# Isolation.net
KiCad netlist of a schematic drawn in Altium Designer
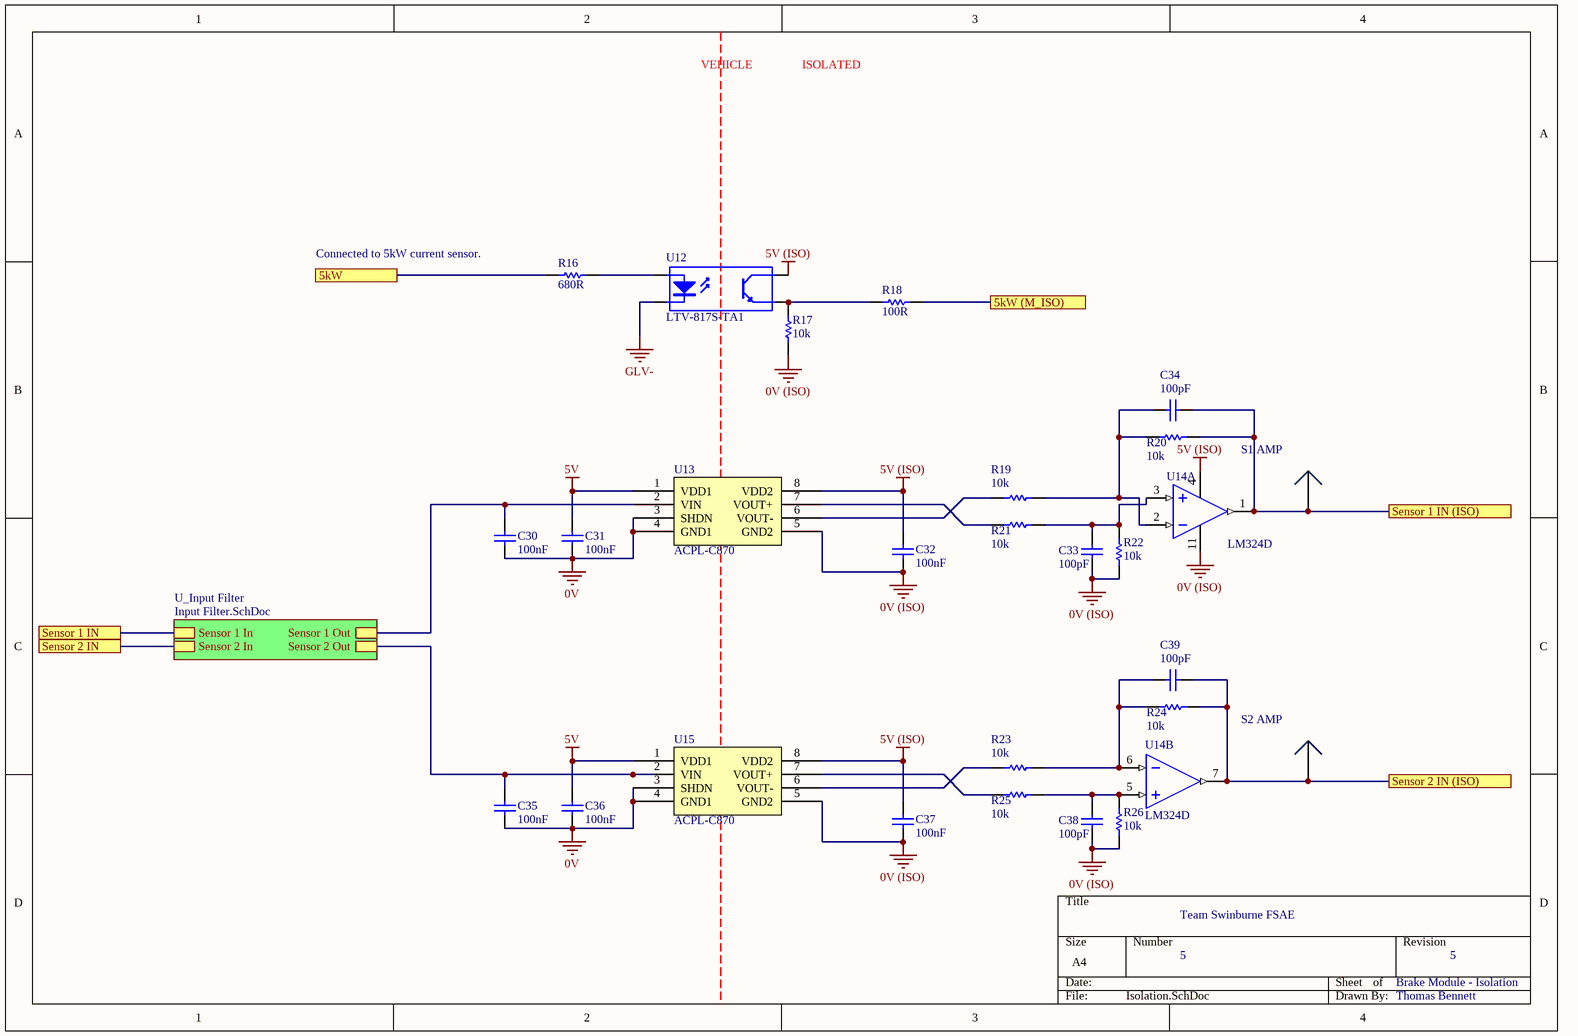
[diagram p0: Isolation.SchDoc]

(export (version "E")
  (design (tool "Eeschema 10.0.6"))
  (components
    (comp (ref "C30")
      (value "100nF")
      (footprint "0805")
      (fields
        (field (name "PART NUMBER") "GCM21BR71H104KA37L")
        (field (name "TOLERANCE") "±10%")
        (field (name "MANUFACTURER") "muRata")
      )
      (libsource (lib "ts_20-standard-library") (part "Capacitor"))
    )
    (comp (ref "C31")
      (value "100nF")
      (footprint "0805")
      (fields
        (field (name "PART NUMBER") "GCM21BR71H104KA37L")
        (field (name "TOLERANCE") "±10%")
        (field (name "MANUFACTURER") "muRata")
      )
      (libsource (lib "ts_20-standard-library") (part "Capacitor"))
    )
    (comp (ref "C32")
      (value "100nF")
      (footprint "0805")
      (fields
        (field (name "PART NUMBER") "GCM21BR71H104KA37L")
        (field (name "TOLERANCE") "±10%")
        (field (name "MANUFACTURER") "muRata")
      )
      (libsource (lib "ts_20-standard-library") (part "Capacitor"))
    )
    (comp (ref "C33")
      (value "100pF")
      (footprint "0805")
      (fields
        (field (name "PART NUMBER") "GCM2165C1H101JA16D")
        (field (name "TOLERANCE") "±5%")
        (field (name "MANUFACTURER") "muRata")
      )
      (libsource (lib "ts_20-standard-library") (part "Capacitor"))
    )
    (comp (ref "C34")
      (value "100pF")
      (footprint "0805")
      (fields
        (field (name "PART NUMBER") "GCM2165C1H101JA16D")
        (field (name "TOLERANCE") "±5%")
        (field (name "MANUFACTURER") "muRata")
      )
      (libsource (lib "ts_20-standard-library") (part "Capacitor"))
    )
    (comp (ref "C35")
      (value "100nF")
      (footprint "0805")
      (fields
        (field (name "PART NUMBER") "GCM21BR71H104KA37L")
        (field (name "TOLERANCE") "±10%")
        (field (name "MANUFACTURER") "muRata")
      )
      (libsource (lib "ts_20-standard-library") (part "Capacitor"))
    )
    (comp (ref "C36")
      (value "100nF")
      (footprint "0805")
      (fields
        (field (name "PART NUMBER") "GCM21BR71H104KA37L")
        (field (name "TOLERANCE") "±10%")
        (field (name "MANUFACTURER") "muRata")
      )
      (libsource (lib "ts_20-standard-library") (part "Capacitor"))
    )
    (comp (ref "C37")
      (value "100nF")
      (footprint "0805")
      (fields
        (field (name "PART NUMBER") "GCM21BR71H104KA37L")
        (field (name "TOLERANCE") "±10%")
        (field (name "MANUFACTURER") "muRata")
      )
      (libsource (lib "ts_20-standard-library") (part "Capacitor"))
    )
    (comp (ref "C38")
      (value "100pF")
      (footprint "0805")
      (fields
        (field (name "PART NUMBER") "GCM2165C1H101JA16D")
        (field (name "TOLERANCE") "±5%")
        (field (name "MANUFACTURER") "muRata")
      )
      (libsource (lib "ts_20-standard-library") (part "Capacitor"))
    )
    (comp (ref "C39")
      (value "100pF")
      (footprint "0805")
      (fields
        (field (name "PART NUMBER") "GCM2165C1H101JA16D")
        (field (name "TOLERANCE") "±5%")
        (field (name "MANUFACTURER") "muRata")
      )
      (libsource (lib "ts_20-standard-library") (part "Capacitor"))
    )
    (comp (ref "R16")
      (value "680R")
      (footprint "0805")
      (fields
        (field (name "PART NUMBER") "RC0805FR07680RL")
        (field (name "MANUFACTURER") "YAGEO")
        (field (name "TOLERANCE") "0.01")
      )
      (libsource (lib "ts_20-standard-library") (part "Resistor"))
    )
    (comp (ref "R17")
      (value "10k")
      (footprint "0805")
      (fields
        (field (name "PART NUMBER") "RC0805FR0710KL")
        (field (name "MANUFACTURER") "YAGEO")
        (field (name "TOLERANCE") "0.01")
      )
      (libsource (lib "ts_20-standard-library") (part "Resistor"))
    )
    (comp (ref "R18")
      (value "100R")
      (footprint "0805")
      (fields
        (field (name "PART NUMBER") "RC0805FR07100RL")
        (field (name "MANUFACTURER") "YAGEO")
        (field (name "TOLERANCE") "0.01")
      )
      (libsource (lib "ts_20-standard-library") (part "Resistor"))
    )
    (comp (ref "R19")
      (value "10k")
      (footprint "0805")
      (fields
        (field (name "PART NUMBER") "RC0805FR0710KL")
        (field (name "MANUFACTURER") "YAGEO")
        (field (name "TOLERANCE") "0.01")
      )
      (libsource (lib "ts_20-standard-library") (part "Resistor"))
    )
    (comp (ref "R20")
      (value "10k")
      (footprint "0805")
      (fields
        (field (name "PART NUMBER") "RC0805FR0710KL")
        (field (name "MANUFACTURER") "YAGEO")
        (field (name "TOLERANCE") "0.01")
      )
      (libsource (lib "ts_20-standard-library") (part "Resistor"))
    )
    (comp (ref "R21")
      (value "10k")
      (footprint "0805")
      (fields
        (field (name "PART NUMBER") "RC0805FR0710KL")
        (field (name "MANUFACTURER") "YAGEO")
        (field (name "TOLERANCE") "0.01")
      )
      (libsource (lib "ts_20-standard-library") (part "Resistor"))
    )
    (comp (ref "R22")
      (value "10k")
      (footprint "0805")
      (fields
        (field (name "PART NUMBER") "RC0805FR0710KL")
        (field (name "MANUFACTURER") "YAGEO")
        (field (name "TOLERANCE") "0.01")
      )
      (libsource (lib "ts_20-standard-library") (part "Resistor"))
    )
    (comp (ref "R23")
      (value "10k")
      (footprint "0805")
      (fields
        (field (name "PART NUMBER") "RC0805FR0710KL")
        (field (name "MANUFACTURER") "YAGEO")
        (field (name "TOLERANCE") "0.01")
      )
      (libsource (lib "ts_20-standard-library") (part "Resistor"))
    )
    (comp (ref "R24")
      (value "10k")
      (footprint "0805")
      (fields
        (field (name "PART NUMBER") "RC0805FR0710KL")
        (field (name "MANUFACTURER") "YAGEO")
        (field (name "TOLERANCE") "0.01")
      )
      (libsource (lib "ts_20-standard-library") (part "Resistor"))
    )
    (comp (ref "R25")
      (value "10k")
      (footprint "0805")
      (fields
        (field (name "PART NUMBER") "RC0805FR0710KL")
        (field (name "MANUFACTURER") "YAGEO")
        (field (name "TOLERANCE") "0.01")
      )
      (libsource (lib "ts_20-standard-library") (part "Resistor"))
    )
    (comp (ref "R26")
      (value "10k")
      (footprint "0805")
      (fields
        (field (name "PART NUMBER") "RC0805FR0710KL")
        (field (name "MANUFACTURER") "YAGEO")
        (field (name "TOLERANCE") "0.01")
      )
      (libsource (lib "ts_20-standard-library") (part "Resistor"))
    )
    (comp (ref "S1 AMP")
      (value "0mm")
      (footprint "SMD Test Point")
      (fields (field (name "PART NUMBER") "SMD Test Point") (field (name "CONTACT") "NA"))
      (libsource (lib "ts_20-standard-connectors") (part "Test Point"))
    )
    (comp (ref "S2 AMP")
      (value "0mm")
      (footprint "SMD Test Point")
      (fields (field (name "PART NUMBER") "SMD Test Point") (field (name "CONTACT") "NA"))
      (libsource (lib "ts_20-standard-connectors") (part "Test Point"))
    )
    (comp (ref "U12")
      (value "LTV-817S-TA1")
      (footprint "ON 4-SMD")
      (description "35V 50ma Optocoupler (VF=1.2V)")
      (fields
        (field (name "MANUFACTURER") "Lite-On Inc")
        (field (name "DIGIKEY PART NUMBER") "160-1893-2-ND")
      )
      (libsource (lib "ts_20-standard-library") (part "LTV-817S-TA1"))
    )
    (comp (ref "U13")
      (value "ACPL-C870")
      (footprint "BROAD 8-SOIC")
      (description "Isolation Amplifier 1 Circuit Differential 8-SO")
      (fields
        (field (name "MANUFACTURER") "Broadcom Limited")
        (field (name "DIGIKEY PART NUMBER") "516-2578-5-ND")
      )
      (libsource (lib "ts_20-standard-library") (part "ACPL-C870"))
    )
    (comp (ref "U14")
      (value "LM324D")
      (footprint "TI 14-SOIC")
      (description "IC OPAMP GP 4 CIRCUIT 14SOIC")
      (fields
        (field (name "MANUFACTURER") "Texas Instruments")
        (field (name "DIGIKEY PART NUMBER") "296-1390-5-ND")
      )
      (libsource (lib "ts_20-standard-library") (part "LM324D"))
    )
    (comp (ref "U15")
      (value "ACPL-C870")
      (footprint "BROAD 8-SOIC")
      (description "Isolation Amplifier 1 Circuit Differential 8-SO")
      (fields
        (field (name "MANUFACTURER") "Broadcom Limited")
        (field (name "DIGIKEY PART NUMBER") "516-2578-5-ND")
      )
      (libsource (lib "ts_20-standard-library") (part "ACPL-C870"))
    )
  )
  (nets
    (net (code "1") (name "/5kW") (class "Default")
      (node (ref "R16") (pin "2") (pinfunction "2_2") (pintype "passive"))
    )
    (net (code "2") (name "/5kW (M_ISO)") (class "Default")
      (node (ref "R18") (pin "1") (pinfunction "1_1") (pintype "passive"))
    )
    (net (code "4") (name "/Sensor 1 IN (ISO)") (class "Default")
      (node (ref "C34") (pin "1") (pinfunction "1_1") (pintype "passive"))
      (node (ref "R20") (pin "2") (pinfunction "2_2") (pintype "passive"))
      (node (ref "S1 AMP") (pin "1") (pinfunction "1_1") (pintype "passive"))
      (node (ref "U14") (pin "1") (pinfunction "1OUT_1") (pintype "output"))
    )
    (net (code "5") (name "/Sensor 1 Out") (class "Default")
      (node (ref "C30") (pin "2") (pinfunction "2_2") (pintype "passive"))
      (node (ref "U13") (pin "2") (pinfunction "VIN_2") (pintype "passive"))
    )
    (net (code "7") (name "/Sensor 2 IN (ISO)") (class "Default")
      (node (ref "C39") (pin "1") (pinfunction "1_1") (pintype "passive"))
      (node (ref "R24") (pin "2") (pinfunction "2_2") (pintype "passive"))
      (node (ref "S2 AMP") (pin "1") (pinfunction "1_1") (pintype "passive"))
      (node (ref "U14") (pin "7") (pinfunction "2OUT_7") (pintype "output"))
    )
    (net (code "8") (name "/Sensor 2 Out") (class "Default")
      (node (ref "C35") (pin "2") (pinfunction "2_2") (pintype "passive"))
      (node (ref "U15") (pin "2") (pinfunction "VIN_2") (pintype "passive"))
    )
    (net (code "9") (name "0V") (class "Default")
      (node (ref "C30") (pin "1") (pinfunction "1_1") (pintype "passive"))
      (node (ref "C31") (pin "1") (pinfunction "1_1") (pintype "passive"))
      (node (ref "C35") (pin "1") (pinfunction "1_1") (pintype "passive"))
      (node (ref "C36") (pin "1") (pinfunction "1_1") (pintype "passive"))
      (node (ref "U13") (pin "3") (pinfunction "SHDN_3") (pintype "passive"))
      (node (ref "U13") (pin "4") (pinfunction "GND1_4") (pintype "passive"))
      (node (ref "U15") (pin "3") (pinfunction "SHDN_3") (pintype "passive"))
      (node (ref "U15") (pin "4") (pinfunction "GND1_4") (pintype "passive"))
    )
    (net (code "10") (name "0V (ISO)") (class "Default")
      (node (ref "C32") (pin "1") (pinfunction "1_1") (pintype "passive"))
      (node (ref "C33") (pin "1") (pinfunction "1_1") (pintype "passive"))
      (node (ref "C37") (pin "1") (pinfunction "1_1") (pintype "passive"))
      (node (ref "C38") (pin "1") (pinfunction "1_1") (pintype "passive"))
      (node (ref "R17") (pin "1") (pinfunction "1_1") (pintype "passive"))
      (node (ref "R22") (pin "1") (pinfunction "1_1") (pintype "passive"))
      (node (ref "R26") (pin "1") (pinfunction "1_1") (pintype "passive"))
      (node (ref "U13") (pin "5") (pinfunction "GND2_5") (pintype "passive"))
      (node (ref "U14") (pin "11") (pinfunction "GND_11") (pintype "power_in"))
      (node (ref "U15") (pin "5") (pinfunction "GND2_5") (pintype "passive"))
    )
    (net (code "11") (name "5V") (class "Default")
      (node (ref "C31") (pin "2") (pinfunction "2_2") (pintype "passive"))
      (node (ref "C36") (pin "2") (pinfunction "2_2") (pintype "passive"))
      (node (ref "U13") (pin "1") (pinfunction "VDD1_1") (pintype "passive"))
      (node (ref "U15") (pin "1") (pinfunction "VDD1_1") (pintype "passive"))
    )
    (net (code "12") (name "5V (ISO)") (class "Default")
      (node (ref "C32") (pin "2") (pinfunction "2_2") (pintype "passive"))
      (node (ref "C37") (pin "2") (pinfunction "2_2") (pintype "passive"))
      (node (ref "U12") (pin "4") (pinfunction "C_4") (pintype "passive"))
      (node (ref "U13") (pin "8") (pinfunction "VDD2_8") (pintype "passive"))
      (node (ref "U14") (pin "4") (pinfunction "VCC_4") (pintype "power_in"))
      (node (ref "U15") (pin "8") (pinfunction "VDD2_8") (pintype "passive"))
    )
    (net (code "13") (name "GLV-") (class "Default")
      (node (ref "U12") (pin "2") (pinfunction "K_2") (pintype "passive"))
    )
    (net (code "14") (name "Net-(C33-Pad2)") (class "Default")
      (node (ref "C33") (pin "2") (pinfunction "2_2") (pintype "passive"))
      (node (ref "R21") (pin "2") (pinfunction "2_2") (pintype "passive"))
      (node (ref "R22") (pin "2") (pinfunction "2_2") (pintype "passive"))
      (node (ref "U14") (pin "3") (pinfunction "1IN+_3") (pintype "input"))
    )
    (net (code "15") (name "Net-(C34-Pad2)") (class "Default")
      (node (ref "C34") (pin "2") (pinfunction "2_2") (pintype "passive"))
      (node (ref "R19") (pin "2") (pinfunction "2_2") (pintype "passive"))
      (node (ref "R20") (pin "1") (pinfunction "1_1") (pintype "passive"))
      (node (ref "U14") (pin "2") (pinfunction "1IN+_2") (pintype "input"))
    )
    (net (code "16") (name "Net-(U12-A)") (class "Default")
      (node (ref "R16") (pin "1") (pinfunction "1_1") (pintype "passive"))
      (node (ref "U12") (pin "1") (pinfunction "A_1") (pintype "passive"))
    )
    (net (code "17") (name "Net-(U12-E)") (class "Default")
      (node (ref "R17") (pin "2") (pinfunction "2_2") (pintype "passive"))
      (node (ref "R18") (pin "2") (pinfunction "2_2") (pintype "passive"))
      (node (ref "U12") (pin "3") (pinfunction "E_3") (pintype "passive"))
    )
    (net (code "18") (name "Net-(U13-VOUT+)") (class "Default")
      (node (ref "R21") (pin "1") (pinfunction "1_1") (pintype "passive"))
      (node (ref "U13") (pin "7") (pinfunction "VOUT+_7") (pintype "passive"))
    )
    (net (code "19") (name "Net-(U13-VOUT-)") (class "Default")
      (node (ref "R19") (pin "1") (pinfunction "1_1") (pintype "passive"))
      (node (ref "U13") (pin "6") (pinfunction "VOUT-_6") (pintype "passive"))
    )
    (net (code "20") (name "Net-(U14B-2IN+)") (class "Default")
      (node (ref "C38") (pin "2") (pinfunction "2_2") (pintype "passive"))
      (node (ref "R25") (pin "2") (pinfunction "2_2") (pintype "passive"))
      (node (ref "R26") (pin "2") (pinfunction "2_2") (pintype "passive"))
      (node (ref "U14") (pin "5") (pinfunction "2IN+_5") (pintype "input"))
    )
    (net (code "21") (name "Net-(U14B-2IN-)") (class "Default")
      (node (ref "C39") (pin "2") (pinfunction "2_2") (pintype "passive"))
      (node (ref "R23") (pin "2") (pinfunction "2_2") (pintype "passive"))
      (node (ref "R24") (pin "1") (pinfunction "1_1") (pintype "passive"))
      (node (ref "U14") (pin "6") (pinfunction "2IN-_6") (pintype "input"))
    )
    (net (code "22") (name "Net-(U15-VOUT+)") (class "Default")
      (node (ref "R25") (pin "1") (pinfunction "1_1") (pintype "passive"))
      (node (ref "U15") (pin "7") (pinfunction "VOUT+_7") (pintype "passive"))
    )
    (net (code "23") (name "Net-(U15-VOUT-)") (class "Default")
      (node (ref "R23") (pin "1") (pinfunction "1_1") (pintype "passive"))
      (node (ref "U15") (pin "6") (pinfunction "VOUT-_6") (pintype "passive"))
    )
  )
)
